# v1.net
KiCad netlist of a schematic drawn in EAGLE
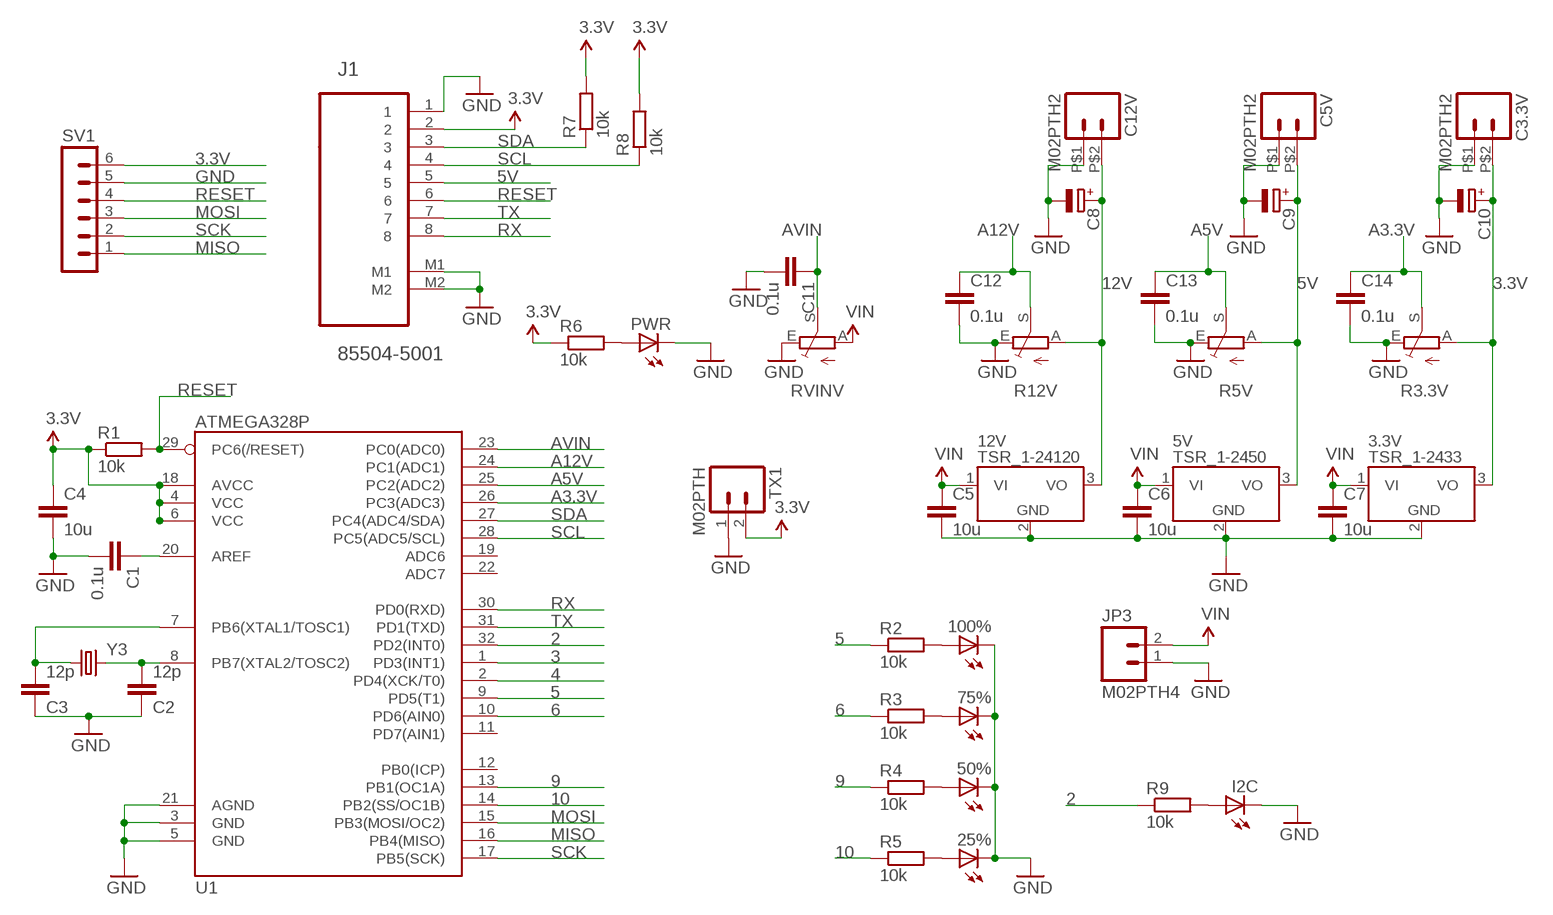
[diagram p0: schematic, sheet 1]

(export (version "E")
  (design (tool "Eeschema 10.0.6"))
  (components
    (comp (ref "3.3V")
      (value "TSR_1-2433")
      (footprint "eagle-import:TSR-1")
      (libsource (lib "eagle-import") (part "TSR_1-2433"))
    )
    (comp (ref "5V")
      (value "TSR_1-2450")
      (footprint "eagle-import:TSR-1")
      (libsource (lib "eagle-import") (part "TSR_1-2450"))
    )
    (comp (ref "12V")
      (value "TSR_1-24120")
      (footprint "eagle-import:TSR-1")
      (libsource (lib "eagle-import") (part "TSR_1-24120"))
    )
    (comp (ref "25%")
      (value "LEDSML0805")
      (footprint "eagle-import:SML0805")
      (libsource (lib "eagle-import") (part "LEDSML0805"))
    )
    (comp (ref "50%")
      (value "LEDSML0805")
      (footprint "eagle-import:SML0805")
      (libsource (lib "eagle-import") (part "LEDSML0805"))
    )
    (comp (ref "75%")
      (value "LEDSML0805")
      (footprint "eagle-import:SML0805")
      (libsource (lib "eagle-import") (part "LEDSML0805"))
    )
    (comp (ref "100%")
      (value "LEDSML0805")
      (footprint "eagle-import:SML0805")
      (libsource (lib "eagle-import") (part "LEDSML0805"))
    )
    (comp (ref "C1")
      (value "0.1u")
      (footprint "eagle-import:C0805")
      (libsource (lib "eagle-import") (part "C-EUC0805"))
    )
    (comp (ref "C2")
      (value "12p")
      (footprint "eagle-import:C0805")
      (libsource (lib "eagle-import") (part "C-EUC0805"))
    )
    (comp (ref "C3")
      (value "12p")
      (footprint "eagle-import:C0805")
      (libsource (lib "eagle-import") (part "C-EUC0805"))
    )
    (comp (ref "C3.3V")
      (value "M02PTH2")
      (footprint "eagle-import:1X02_BIG")
      (libsource (lib "eagle-import") (part "M02PTH2"))
    )
    (comp (ref "C4")
      (value "10u")
      (footprint "eagle-import:C0805")
      (libsource (lib "eagle-import") (part "C-EUC0805"))
    )
    (comp (ref "C5")
      (value "10u")
      (footprint "eagle-import:C0805")
      (libsource (lib "eagle-import") (part "C-EUC0805"))
    )
    (comp (ref "C5V")
      (value "M02PTH2")
      (footprint "eagle-import:1X02_BIG")
      (libsource (lib "eagle-import") (part "M02PTH2"))
    )
    (comp (ref "C6")
      (value "10u")
      (footprint "eagle-import:C0805")
      (libsource (lib "eagle-import") (part "C-EUC0805"))
    )
    (comp (ref "C7")
      (value "10u")
      (footprint "eagle-import:C0805")
      (libsource (lib "eagle-import") (part "C-EUC0805"))
    )
    (comp (ref "C8")
      (value "CPOL-EUE3.5-8")
      (footprint "eagle-import:E3,5-8")
      (libsource (lib "eagle-import") (part "CPOL-EUE3.5-8"))
    )
    (comp (ref "C9")
      (value "CPOL-EUE3.5-8")
      (footprint "eagle-import:E3,5-8")
      (libsource (lib "eagle-import") (part "CPOL-EUE3.5-8"))
    )
    (comp (ref "C10")
      (value "CPOL-EUE3.5-8")
      (footprint "eagle-import:E3,5-8")
      (libsource (lib "eagle-import") (part "CPOL-EUE3.5-8"))
    )
    (comp (ref "C11")
      (value "0.1u")
      (footprint "eagle-import:C0805")
      (libsource (lib "eagle-import") (part "C-EUC0805"))
    )
    (comp (ref "C12")
      (value "0.1u")
      (footprint "eagle-import:C0805")
      (libsource (lib "eagle-import") (part "C-EUC0805"))
    )
    (comp (ref "C12V")
      (value "M02PTH2")
      (footprint "eagle-import:1X02_BIG")
      (libsource (lib "eagle-import") (part "M02PTH2"))
    )
    (comp (ref "C13")
      (value "0.1u")
      (footprint "eagle-import:C0805")
      (libsource (lib "eagle-import") (part "C-EUC0805"))
    )
    (comp (ref "C14")
      (value "0.1u")
      (footprint "eagle-import:C0805")
      (libsource (lib "eagle-import") (part "C-EUC0805"))
    )
    (comp (ref "I2C")
      (value "LEDSML0805")
      (footprint "eagle-import:SML0805")
      (libsource (lib "eagle-import") (part "LEDSML0805"))
    )
    (comp (ref "J1")
      (value "85504-5001")
      (footprint "eagle-import:MOLEX_85504-5001")
      (libsource (lib "eagle-import") (part "85504-5001"))
    )
    (comp (ref "JP3")
      (value "M02PTH4")
      (footprint "eagle-import:1X02_XTRA_BIG")
      (libsource (lib "eagle-import") (part "M02PTH4"))
    )
    (comp (ref "PWR")
      (value "LEDSML0805")
      (footprint "eagle-import:SML0805")
      (libsource (lib "eagle-import") (part "LEDSML0805"))
    )
    (comp (ref "R1")
      (value "10k")
      (footprint "eagle-import:R0805")
      (libsource (lib "eagle-import") (part "R-EU_R0805"))
    )
    (comp (ref "R2")
      (value "10k")
      (footprint "eagle-import:R0805")
      (libsource (lib "eagle-import") (part "R-EU_R0805"))
    )
    (comp (ref "R3")
      (value "10k")
      (footprint "eagle-import:R0805")
      (libsource (lib "eagle-import") (part "R-EU_R0805"))
    )
    (comp (ref "R3.3V")
      (value "TRIM_EU-B64W")
      (footprint "eagle-import:B64W")
      (libsource (lib "eagle-import") (part "TRIM_EU-B64W"))
    )
    (comp (ref "R4")
      (value "10k")
      (footprint "eagle-import:R0805")
      (libsource (lib "eagle-import") (part "R-EU_R0805"))
    )
    (comp (ref "R5")
      (value "10k")
      (footprint "eagle-import:R0805")
      (libsource (lib "eagle-import") (part "R-EU_R0805"))
    )
    (comp (ref "R5V")
      (value "TRIM_EU-B64W")
      (footprint "eagle-import:B64W")
      (libsource (lib "eagle-import") (part "TRIM_EU-B64W"))
    )
    (comp (ref "R6")
      (value "10k")
      (footprint "eagle-import:R0805")
      (libsource (lib "eagle-import") (part "R-EU_R0805"))
    )
    (comp (ref "R7")
      (value "10k")
      (footprint "eagle-import:R0805")
      (libsource (lib "eagle-import") (part "R-EU_R0805"))
    )
    (comp (ref "R8")
      (value "10k")
      (footprint "eagle-import:R0805")
      (libsource (lib "eagle-import") (part "R-EU_R0805"))
    )
    (comp (ref "R9")
      (value "10k")
      (footprint "eagle-import:R0805")
      (libsource (lib "eagle-import") (part "R-EU_R0805"))
    )
    (comp (ref "R12V")
      (value "TRIM_EU-B64W")
      (footprint "eagle-import:B64W")
      (libsource (lib "eagle-import") (part "TRIM_EU-B64W"))
    )
    (comp (ref "RVINV")
      (value "TRIM_EU-B64W")
      (footprint "eagle-import:B64W")
      (libsource (lib "eagle-import") (part "TRIM_EU-B64W"))
    )
    (comp (ref "SV1")
      (value "MA06-1")
      (footprint "eagle-import:MA06-1")
      (libsource (lib "eagle-import") (part "MA06-1"))
    )
    (comp (ref "TX1")
      (value "M02PTH")
      (footprint "eagle-import:1X02")
      (libsource (lib "eagle-import") (part "M02PTH"))
    )
    (comp (ref "U1")
      (value "ATMEGA328P")
      (footprint "eagle-import:TQFP32-08")
      (libsource (lib "eagle-import") (part "ATMEGA328_SMT"))
    )
    (comp (ref "Y3")
      (value "CRYSTALCRYSTAL-SMD-5X3-LARGEPAD")
      (footprint "eagle-import:CRYSTAL-SMD-5X3")
      (libsource (lib "eagle-import") (part "CRYSTALCRYSTAL-SMD-5X3-LARGEPAD"))
    )
  )
  (nets
    (net (code "1") (name "/2") (class "Default")
      (node (ref "R9") (pin "1") (pinfunction "1_1") (pintype "passive"))
      (node (ref "U1") (pin "32") (pinfunction "PD2(INT0)_32") (pintype "bidirectional"))
    )
    (net (code "2") (name "/3") (class "Default")
      (node (ref "U1") (pin "1") (pinfunction "PD3(INT1)_1") (pintype "bidirectional"))
    )
    (net (code "3") (name "/4") (class "Default")
      (node (ref "U1") (pin "2") (pinfunction "PD4(XCK/T0)_2") (pintype "bidirectional"))
    )
    (net (code "4") (name "/5") (class "Default")
      (node (ref "R2") (pin "1") (pinfunction "1_1") (pintype "passive"))
      (node (ref "U1") (pin "9") (pinfunction "PD5(T1)_9") (pintype "bidirectional"))
    )
    (net (code "5") (name "/5V") (class "Default")
      (node (ref "5V") (pin "3") (pinfunction "VO_3") (pintype "power_in"))
      (node (ref "C5V") (pin "P$2") (pinfunction "2_P$2") (pintype "passive"))
      (node (ref "C9") (pin "+") (pinfunction "+_+") (pintype "passive"))
      (node (ref "J1") (pin "5") (pinfunction "5_5") (pintype "bidirectional"))
      (node (ref "R5V") (pin "A") (pinfunction "A_A") (pintype "passive"))
    )
    (net (code "6") (name "/6") (class "Default")
      (node (ref "R3") (pin "1") (pinfunction "1_1") (pintype "passive"))
      (node (ref "U1") (pin "10") (pinfunction "PD6(AIN0)_10") (pintype "bidirectional"))
    )
    (net (code "7") (name "/9") (class "Default")
      (node (ref "R4") (pin "1") (pinfunction "1_1") (pintype "passive"))
      (node (ref "U1") (pin "13") (pinfunction "PB1(OC1A)_13") (pintype "bidirectional"))
    )
    (net (code "8") (name "/10") (class "Default")
      (node (ref "R5") (pin "1") (pinfunction "1_1") (pintype "passive"))
      (node (ref "U1") (pin "14") (pinfunction "PB2(SS/OC1B)_14") (pintype "bidirectional"))
    )
    (net (code "9") (name "/12V") (class "Default")
      (node (ref "12V") (pin "3") (pinfunction "VO_3") (pintype "power_in"))
      (node (ref "C12V") (pin "P$2") (pinfunction "2_P$2") (pintype "passive"))
      (node (ref "C8") (pin "+") (pinfunction "+_+") (pintype "passive"))
      (node (ref "R12V") (pin "A") (pinfunction "A_A") (pintype "passive"))
    )
    (net (code "10") (name "/A3.3V") (class "Default")
      (node (ref "C14") (pin "1") (pinfunction "1_1") (pintype "passive"))
      (node (ref "R3.3V") (pin "S") (pinfunction "S_S") (pintype "passive"))
      (node (ref "U1") (pin "26") (pinfunction "PC3(ADC3)_26") (pintype "bidirectional"))
    )
    (net (code "11") (name "/A5V") (class "Default")
      (node (ref "C13") (pin "1") (pinfunction "1_1") (pintype "passive"))
      (node (ref "R5V") (pin "S") (pinfunction "S_S") (pintype "passive"))
      (node (ref "U1") (pin "25") (pinfunction "PC2(ADC2)_25") (pintype "bidirectional"))
    )
    (net (code "12") (name "/A12V") (class "Default")
      (node (ref "C12") (pin "1") (pinfunction "1_1") (pintype "passive"))
      (node (ref "R12V") (pin "S") (pinfunction "S_S") (pintype "passive"))
      (node (ref "U1") (pin "24") (pinfunction "PC1(ADC1)_24") (pintype "bidirectional"))
    )
    (net (code "13") (name "/AVIN") (class "Default")
      (node (ref "C11") (pin "1") (pinfunction "1_1") (pintype "passive"))
      (node (ref "RVINV") (pin "S") (pinfunction "S_S") (pintype "passive"))
      (node (ref "U1") (pin "23") (pinfunction "PC0(ADC0)_23") (pintype "bidirectional"))
    )
    (net (code "14") (name "/MISO") (class "Default")
      (node (ref "SV1") (pin "1") (pinfunction "1_1") (pintype "passive"))
      (node (ref "U1") (pin "16") (pinfunction "PB4(MISO)_16") (pintype "bidirectional"))
    )
    (net (code "15") (name "/MOSI") (class "Default")
      (node (ref "SV1") (pin "3") (pinfunction "3_3") (pintype "passive"))
      (node (ref "U1") (pin "15") (pinfunction "PB3(MOSI/OC2)_15") (pintype "bidirectional"))
    )
    (net (code "16") (name "/RESET") (class "Default")
      (node (ref "J1") (pin "6") (pinfunction "6_6") (pintype "bidirectional"))
      (node (ref "R1") (pin "2") (pinfunction "2_2") (pintype "passive"))
      (node (ref "SV1") (pin "4") (pinfunction "4_4") (pintype "passive"))
      (node (ref "U1") (pin "29") (pinfunction "PC6(/RESET)_29") (pintype "bidirectional"))
    )
    (net (code "17") (name "/RX") (class "Default")
      (node (ref "J1") (pin "8") (pinfunction "8_8") (pintype "bidirectional"))
      (node (ref "U1") (pin "30") (pinfunction "PD0(RXD)_30") (pintype "bidirectional"))
    )
    (net (code "18") (name "/SCK") (class "Default")
      (node (ref "SV1") (pin "2") (pinfunction "2_2") (pintype "passive"))
      (node (ref "U1") (pin "17") (pinfunction "PB5(SCK)_17") (pintype "bidirectional"))
    )
    (net (code "19") (name "/SCL") (class "Default")
      (node (ref "J1") (pin "4") (pinfunction "4_4") (pintype "bidirectional"))
      (node (ref "R8") (pin "1") (pinfunction "1_1") (pintype "passive"))
      (node (ref "U1") (pin "28") (pinfunction "PC5(ADC5/SCL)_28") (pintype "bidirectional"))
    )
    (net (code "20") (name "/SDA") (class "Default")
      (node (ref "J1") (pin "3") (pinfunction "3_3") (pintype "bidirectional"))
      (node (ref "R7") (pin "1") (pinfunction "1_1") (pintype "passive"))
      (node (ref "U1") (pin "27") (pinfunction "PC4(ADC4/SDA)_27") (pintype "bidirectional"))
    )
    (net (code "21") (name "/TX") (class "Default")
      (node (ref "J1") (pin "7") (pinfunction "7_7") (pintype "bidirectional"))
      (node (ref "U1") (pin "31") (pinfunction "PD1(TXD)_31") (pintype "bidirectional"))
    )
    (net (code "22") (name "3.3V") (class "Default")
      (node (ref "3.3V") (pin "3") (pinfunction "VO_3") (pintype "power_in"))
      (node (ref "C10") (pin "+") (pinfunction "+_+") (pintype "passive"))
      (node (ref "C3.3V") (pin "P$2") (pinfunction "2_P$2") (pintype "passive"))
      (node (ref "C4") (pin "1") (pinfunction "1_1") (pintype "passive"))
      (node (ref "J1") (pin "2") (pinfunction "2_2") (pintype "bidirectional"))
      (node (ref "R1") (pin "1") (pinfunction "1_1") (pintype "passive"))
      (node (ref "R3.3V") (pin "A") (pinfunction "A_A") (pintype "passive"))
      (node (ref "R6") (pin "1") (pinfunction "1_1") (pintype "passive"))
      (node (ref "R7") (pin "2") (pinfunction "2_2") (pintype "passive"))
      (node (ref "R8") (pin "2") (pinfunction "2_2") (pintype "passive"))
      (node (ref "SV1") (pin "6") (pinfunction "6_6") (pintype "passive"))
      (node (ref "TX1") (pin "2") (pinfunction "2_2") (pintype "passive"))
      (node (ref "U1") (pin "18") (pinfunction "AVCC_18") (pintype "bidirectional"))
      (node (ref "U1") (pin "4") (pinfunction "VCC_4") (pintype "bidirectional"))
      (node (ref "U1") (pin "6") (pinfunction "VCC_6") (pintype "bidirectional"))
    )
    (net (code "23") (name "GND") (class "Default")
      (node (ref "100%") (pin "C") (pinfunction "C_C") (pintype "passive"))
      (node (ref "12V") (pin "2") (pinfunction "GND_2") (pintype "power_in"))
      (node (ref "25%") (pin "C") (pinfunction "C_C") (pintype "passive"))
      (node (ref "3.3V") (pin "2") (pinfunction "GND_2") (pintype "power_in"))
      (node (ref "50%") (pin "C") (pinfunction "C_C") (pintype "passive"))
      (node (ref "5V") (pin "2") (pinfunction "GND_2") (pintype "power_in"))
      (node (ref "75%") (pin "C") (pinfunction "C_C") (pintype "passive"))
      (node (ref "C1") (pin "2") (pinfunction "2_2") (pintype "passive"))
      (node (ref "C10") (pin "-") (pinfunction "-_-") (pintype "passive"))
      (node (ref "C11") (pin "2") (pinfunction "2_2") (pintype "passive"))
      (node (ref "C12") (pin "2") (pinfunction "2_2") (pintype "passive"))
      (node (ref "C12V") (pin "P$1") (pinfunction "1_P$1") (pintype "passive"))
      (node (ref "C13") (pin "2") (pinfunction "2_2") (pintype "passive"))
      (node (ref "C14") (pin "2") (pinfunction "2_2") (pintype "passive"))
      (node (ref "C2") (pin "1") (pinfunction "1_1") (pintype "passive"))
      (node (ref "C3") (pin "1") (pinfunction "1_1") (pintype "passive"))
      (node (ref "C3.3V") (pin "P$1") (pinfunction "1_P$1") (pintype "passive"))
      (node (ref "C4") (pin "2") (pinfunction "2_2") (pintype "passive"))
      (node (ref "C5") (pin "2") (pinfunction "2_2") (pintype "passive"))
      (node (ref "C5V") (pin "P$1") (pinfunction "1_P$1") (pintype "passive"))
      (node (ref "C6") (pin "2") (pinfunction "2_2") (pintype "passive"))
      (node (ref "C7") (pin "2") (pinfunction "2_2") (pintype "passive"))
      (node (ref "C8") (pin "-") (pinfunction "-_-") (pintype "passive"))
      (node (ref "C9") (pin "-") (pinfunction "-_-") (pintype "passive"))
      (node (ref "I2C") (pin "C") (pinfunction "C_C") (pintype "passive"))
      (node (ref "J1") (pin "1") (pinfunction "1_1") (pintype "bidirectional"))
      (node (ref "J1") (pin "M1") (pinfunction "M1_M1") (pintype "bidirectional"))
      (node (ref "J1") (pin "M2") (pinfunction "M2_M2") (pintype "bidirectional"))
      (node (ref "JP3") (pin "1") (pinfunction "1_1") (pintype "passive"))
      (node (ref "PWR") (pin "C") (pinfunction "C_C") (pintype "passive"))
      (node (ref "R12V") (pin "E") (pinfunction "E_E") (pintype "passive"))
      (node (ref "R3.3V") (pin "E") (pinfunction "E_E") (pintype "passive"))
      (node (ref "R5V") (pin "E") (pinfunction "E_E") (pintype "passive"))
      (node (ref "RVINV") (pin "E") (pinfunction "E_E") (pintype "passive"))
      (node (ref "SV1") (pin "5") (pinfunction "5_5") (pintype "passive"))
      (node (ref "TX1") (pin "1") (pinfunction "1_1") (pintype "passive"))
      (node (ref "U1") (pin "21") (pinfunction "AGND_21") (pintype "bidirectional"))
      (node (ref "U1") (pin "3") (pinfunction "GND_3") (pintype "bidirectional"))
      (node (ref "U1") (pin "5") (pinfunction "GND_5") (pintype "bidirectional"))
    )
    (net (code "24") (name "Net-(25%-PadA)") (class "Default")
      (node (ref "25%") (pin "A") (pinfunction "A_A") (pintype "passive"))
      (node (ref "R5") (pin "2") (pinfunction "2_2") (pintype "passive"))
    )
    (net (code "25") (name "Net-(50%-PadA)") (class "Default")
      (node (ref "50%") (pin "A") (pinfunction "A_A") (pintype "passive"))
      (node (ref "R4") (pin "2") (pinfunction "2_2") (pintype "passive"))
    )
    (net (code "26") (name "Net-(75%-PadA)") (class "Default")
      (node (ref "75%") (pin "A") (pinfunction "A_A") (pintype "passive"))
      (node (ref "R3") (pin "2") (pinfunction "2_2") (pintype "passive"))
    )
    (net (code "27") (name "Net-(100%-PadA)") (class "Default")
      (node (ref "100%") (pin "A") (pinfunction "A_A") (pintype "passive"))
      (node (ref "R2") (pin "2") (pinfunction "2_2") (pintype "passive"))
    )
    (net (code "28") (name "Net-(I2C-PadA)") (class "Default")
      (node (ref "I2C") (pin "A") (pinfunction "A_A") (pintype "passive"))
      (node (ref "R9") (pin "2") (pinfunction "2_2") (pintype "passive"))
    )
    (net (code "29") (name "Net-(PWR-PadA)") (class "Default")
      (node (ref "PWR") (pin "A") (pinfunction "A_A") (pintype "passive"))
      (node (ref "R6") (pin "2") (pinfunction "2_2") (pintype "passive"))
    )
    (net (code "30") (name "Net-(U1-AREF)") (class "Default")
      (node (ref "C1") (pin "1") (pinfunction "1_1") (pintype "passive"))
      (node (ref "U1") (pin "20") (pinfunction "AREF_20") (pintype "bidirectional"))
    )
    (net (code "31") (name "Net-(U1-PB6(XTAL1{slash}TOSC1))") (class "Default")
      (node (ref "C3") (pin "2") (pinfunction "2_2") (pintype "passive"))
      (node (ref "U1") (pin "7") (pinfunction "PB6(XTAL1/TOSC1)_7") (pintype "bidirectional"))
      (node (ref "Y3") (pin "1") (pinfunction "1_1") (pintype "passive"))
    )
    (net (code "32") (name "Net-(U1-PB7(XTAL2{slash}TOSC2))") (class "Default")
      (node (ref "C2") (pin "2") (pinfunction "2_2") (pintype "passive"))
      (node (ref "U1") (pin "8") (pinfunction "PB7(XTAL2/TOSC2)_8") (pintype "bidirectional"))
      (node (ref "Y3") (pin "3") (pinfunction "2_3") (pintype "passive"))
    )
    (net (code "33") (name "VIN") (class "Default")
      (node (ref "12V") (pin "1") (pinfunction "VI_1") (pintype "power_in"))
      (node (ref "3.3V") (pin "1") (pinfunction "VI_1") (pintype "power_in"))
      (node (ref "5V") (pin "1") (pinfunction "VI_1") (pintype "power_in"))
      (node (ref "C5") (pin "1") (pinfunction "1_1") (pintype "passive"))
      (node (ref "C6") (pin "1") (pinfunction "1_1") (pintype "passive"))
      (node (ref "C7") (pin "1") (pinfunction "1_1") (pintype "passive"))
      (node (ref "JP3") (pin "2") (pinfunction "2_2") (pintype "passive"))
      (node (ref "RVINV") (pin "A") (pinfunction "A_A") (pintype "passive"))
    )
    (net (code "34") (name "unconnected-(U1-ADC6-Pad19)") (class "Default")
      (node (ref "U1") (pin "19") (pinfunction "ADC6_19") (pintype "bidirectional"))
    )
    (net (code "35") (name "unconnected-(U1-ADC7-Pad22)") (class "Default")
      (node (ref "U1") (pin "22") (pinfunction "ADC7_22") (pintype "bidirectional"))
    )
    (net (code "36") (name "unconnected-(U1-PB0(ICP)-Pad12)") (class "Default")
      (node (ref "U1") (pin "12") (pinfunction "PB0(ICP)_12") (pintype "bidirectional"))
    )
    (net (code "37") (name "unconnected-(U1-PD7(AIN1)-Pad11)") (class "Default")
      (node (ref "U1") (pin "11") (pinfunction "PD7(AIN1)_11") (pintype "bidirectional"))
    )
  )
)
